# hall.net
KiCad netlist of a schematic drawn in EAGLE
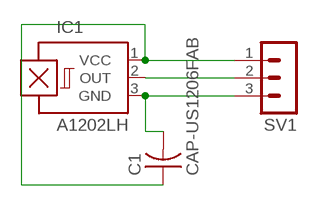
[diagram p0: schematic, sheet 1]

(export (version "E")
  (design (tool "Eeschema 10.0.6"))
  (components
    (comp (ref "C1")
      (value "CAP-US1206FAB")
      (footprint "eagle-import:C1206FAB")
      (libsource (lib "eagle-import") (part "CAP-US1206FAB"))
    )
    (comp (ref "IC1")
      (value "A1202LH")
      (footprint "eagle-import:SOT23-W")
      (libsource (lib "eagle-import") (part "A12?LH02"))
    )
    (comp (ref "SV1")
      (value "MA03-1")
      (footprint "eagle-import:MA03-1")
      (libsource (lib "eagle-import") (part "MA03-1"))
    )
  )
  (nets
    (net (code "1") (name "Net-(IC1-GND)") (class "Default")
      (node (ref "C1") (pin "2") (pinfunction "2_2") (pintype "passive"))
      (node (ref "IC1") (pin "3") (pinfunction "GND_3") (pintype "power_in"))
      (node (ref "SV1") (pin "3") (pinfunction "3_3") (pintype "passive"))
    )
    (net (code "2") (name "Net-(IC1-OUT)") (class "Default")
      (node (ref "IC1") (pin "2") (pinfunction "OUT_2") (pintype "output"))
      (node (ref "SV1") (pin "2") (pinfunction "2_2") (pintype "passive"))
    )
    (net (code "3") (name "Net-(IC1-VCC)") (class "Default")
      (node (ref "C1") (pin "1") (pinfunction "1_1") (pintype "passive"))
      (node (ref "IC1") (pin "1") (pinfunction "VCC_1") (pintype "power_in"))
      (node (ref "SV1") (pin "1") (pinfunction "1_1") (pintype "passive"))
    )
  )
)
